# grissom.net
KiCad netlist of a schematic drawn in EAGLE
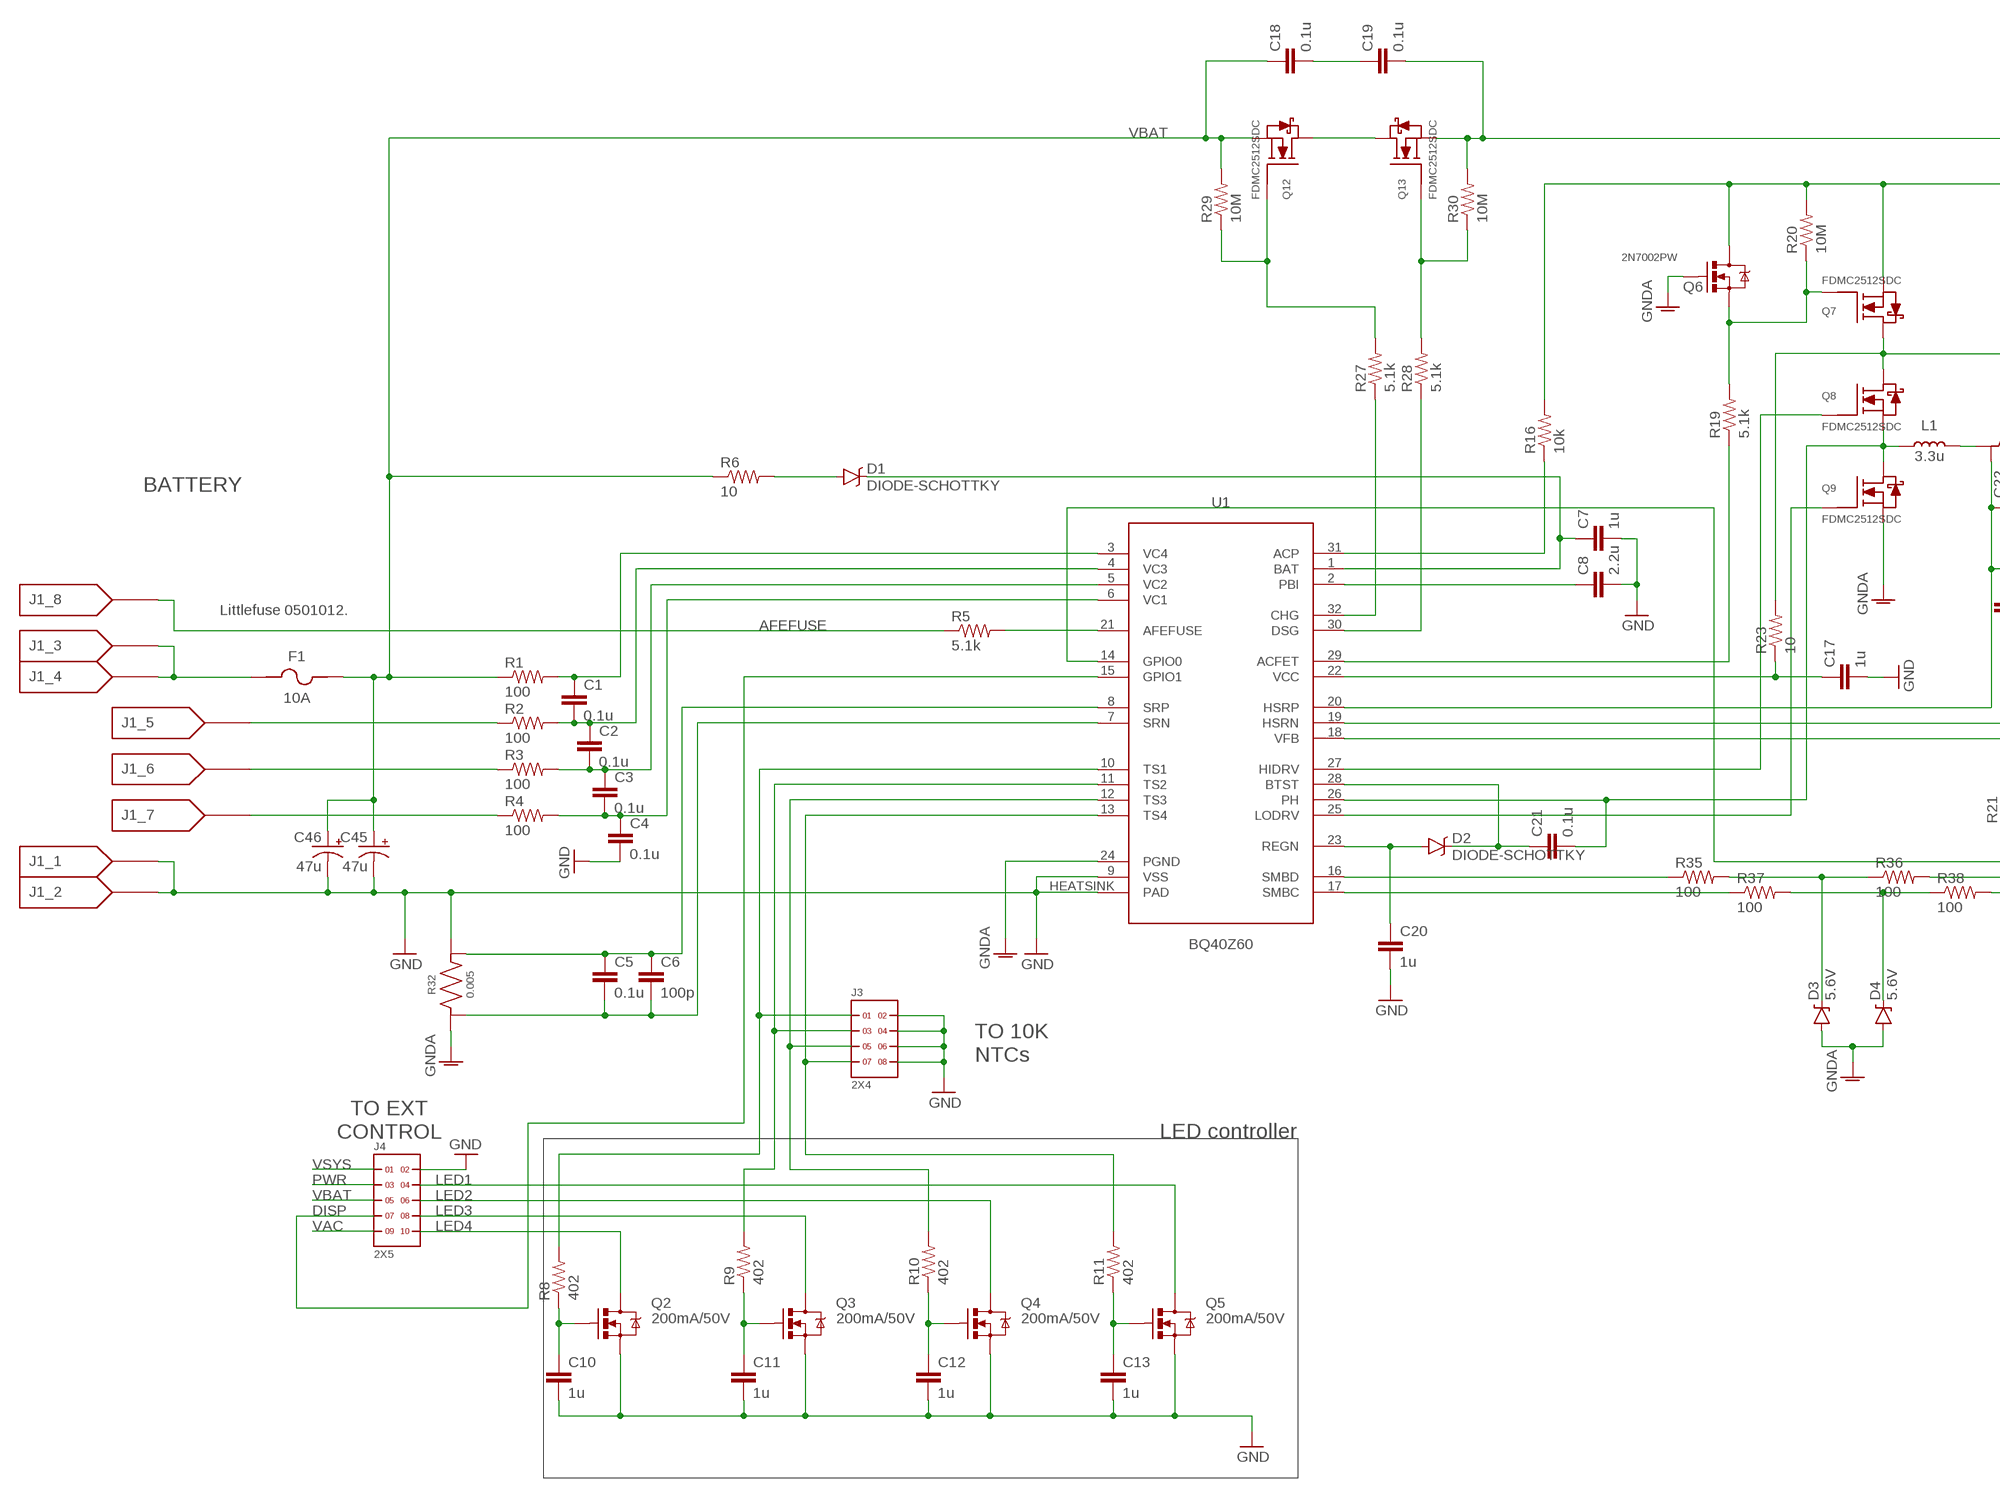
[diagram p0: schematic, sheet 1, part 1 of 2]
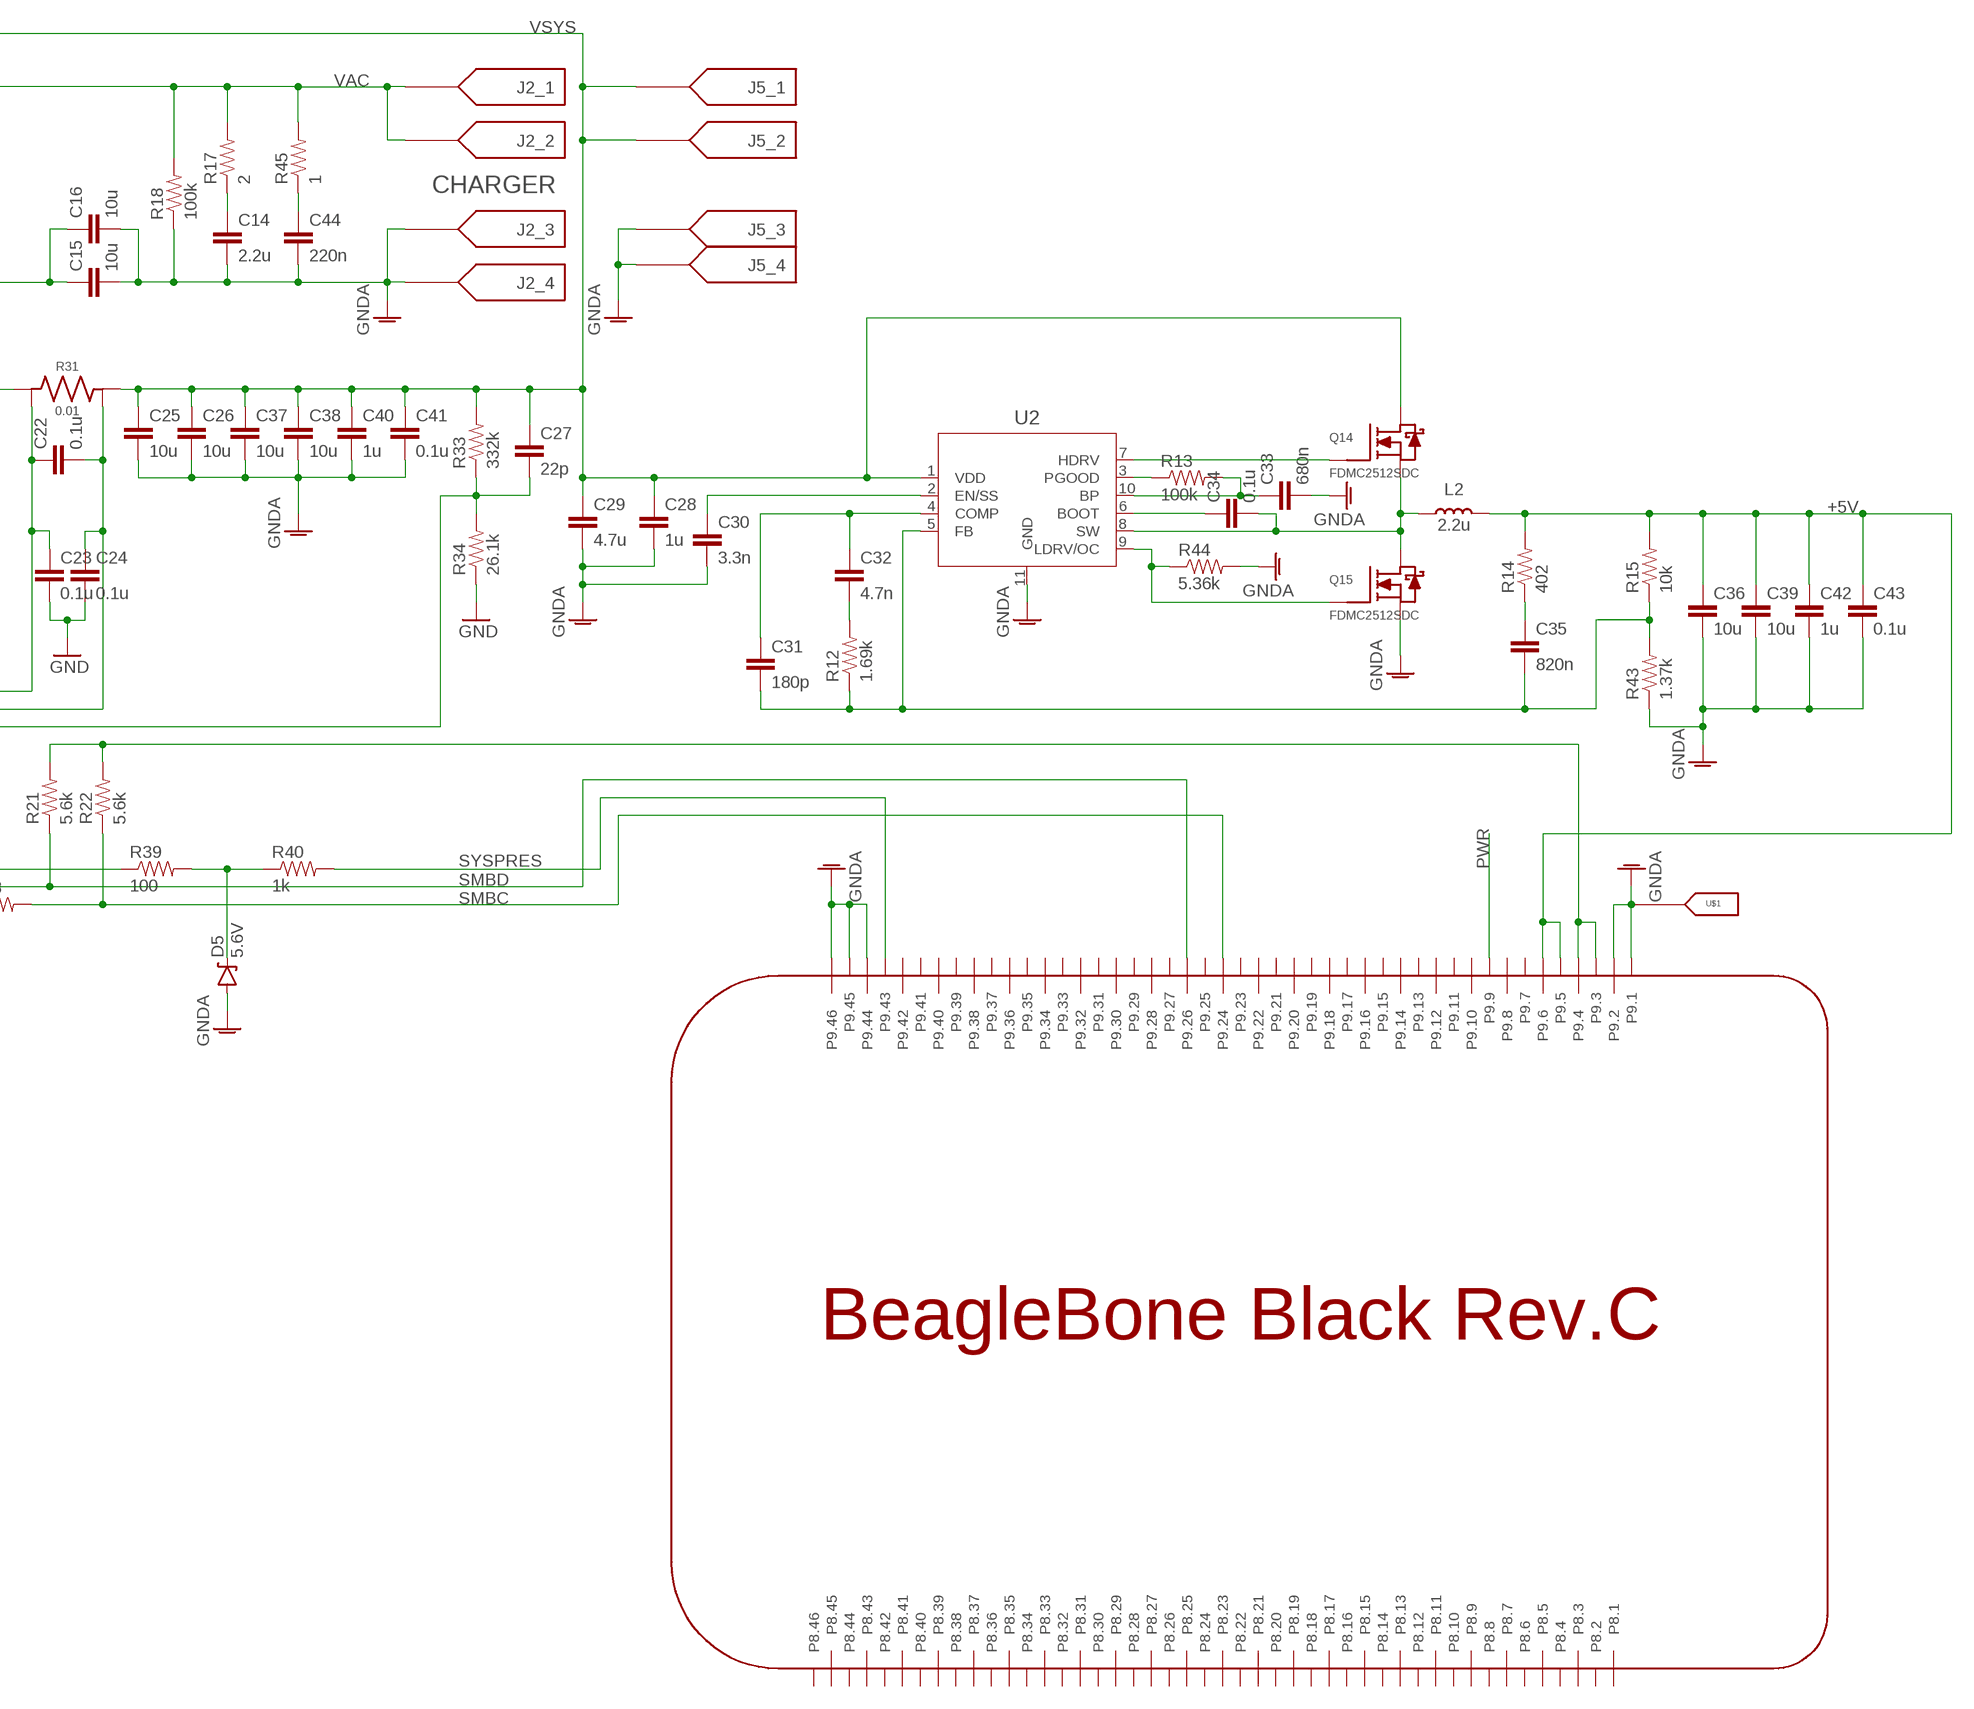
[diagram p1: schematic, sheet 1, part 2 of 2]

(export (version "E")
  (design (tool "Eeschema 10.0.6"))
  (components
    (comp (ref "C1")
      (value "0.1u")
      (footprint "eagle-import:0805")
      (libsource (lib "eagle-import") (part "CAP0805"))
    )
    (comp (ref "C2")
      (value "0.1u")
      (footprint "eagle-import:0805")
      (libsource (lib "eagle-import") (part "CAP0805"))
    )
    (comp (ref "C3")
      (value "0.1u")
      (footprint "eagle-import:0805")
      (libsource (lib "eagle-import") (part "CAP0805"))
    )
    (comp (ref "C4")
      (value "0.1u")
      (footprint "eagle-import:0805")
      (libsource (lib "eagle-import") (part "CAP0805"))
    )
    (comp (ref "C5")
      (value "0.1u")
      (footprint "eagle-import:0805")
      (libsource (lib "eagle-import") (part "CAP0805"))
    )
    (comp (ref "C6")
      (value "100p")
      (footprint "eagle-import:0805")
      (libsource (lib "eagle-import") (part "CAP0805"))
    )
    (comp (ref "C7")
      (value "1u")
      (footprint "eagle-import:0805")
      (libsource (lib "eagle-import") (part "CAP0805"))
    )
    (comp (ref "C8")
      (value "2.2u")
      (footprint "eagle-import:0805")
      (libsource (lib "eagle-import") (part "CAP0805"))
    )
    (comp (ref "C10")
      (value "1u")
      (footprint "eagle-import:0805")
      (libsource (lib "eagle-import") (part "CAP0805"))
    )
    (comp (ref "C11")
      (value "1u")
      (footprint "eagle-import:0805")
      (libsource (lib "eagle-import") (part "CAP0805"))
    )
    (comp (ref "C12")
      (value "1u")
      (footprint "eagle-import:0805")
      (libsource (lib "eagle-import") (part "CAP0805"))
    )
    (comp (ref "C13")
      (value "1u")
      (footprint "eagle-import:0805")
      (libsource (lib "eagle-import") (part "CAP0805"))
    )
    (comp (ref "C14")
      (value "2.2u")
      (footprint "eagle-import:0805")
      (libsource (lib "eagle-import") (part "CAP0805"))
    )
    (comp (ref "C15")
      (value "10u")
      (footprint "eagle-import:1206")
      (libsource (lib "eagle-import") (part "CAP1206"))
    )
    (comp (ref "C16")
      (value "10u")
      (footprint "eagle-import:1206")
      (libsource (lib "eagle-import") (part "CAP1206"))
    )
    (comp (ref "C17")
      (value "1u")
      (footprint "eagle-import:0805")
      (libsource (lib "eagle-import") (part "CAP0805"))
    )
    (comp (ref "C18")
      (value "0.1u")
      (footprint "eagle-import:0805")
      (libsource (lib "eagle-import") (part "CAP0805"))
    )
    (comp (ref "C19")
      (value "0.1u")
      (footprint "eagle-import:0805")
      (libsource (lib "eagle-import") (part "CAP0805"))
    )
    (comp (ref "C20")
      (value "1u")
      (footprint "eagle-import:0805")
      (libsource (lib "eagle-import") (part "CAP0805"))
    )
    (comp (ref "C21")
      (value "0.1u")
      (footprint "eagle-import:0805")
      (libsource (lib "eagle-import") (part "CAP0805"))
    )
    (comp (ref "C22")
      (value "0.1u")
      (footprint "eagle-import:0805")
      (libsource (lib "eagle-import") (part "CAP0805"))
    )
    (comp (ref "C23")
      (value "0.1u")
      (footprint "eagle-import:0805")
      (libsource (lib "eagle-import") (part "CAP0805"))
    )
    (comp (ref "C24")
      (value "0.1u")
      (footprint "eagle-import:0805")
      (libsource (lib "eagle-import") (part "CAP0805"))
    )
    (comp (ref "C25")
      (value "10u")
      (footprint "eagle-import:1206")
      (libsource (lib "eagle-import") (part "CAP1206"))
    )
    (comp (ref "C26")
      (value "10u")
      (footprint "eagle-import:1206")
      (libsource (lib "eagle-import") (part "CAP1206"))
    )
    (comp (ref "C27")
      (value "22p")
      (footprint "eagle-import:0805")
      (libsource (lib "eagle-import") (part "CAP0805"))
    )
    (comp (ref "C28")
      (value "1u")
      (footprint "eagle-import:0805")
      (libsource (lib "eagle-import") (part "CAP0805"))
    )
    (comp (ref "C29")
      (value "4.7u")
      (footprint "eagle-import:0805")
      (libsource (lib "eagle-import") (part "CAP0805"))
    )
    (comp (ref "C30")
      (value "3.3n")
      (footprint "eagle-import:0805")
      (libsource (lib "eagle-import") (part "CAP0805"))
    )
    (comp (ref "C31")
      (value "180p")
      (footprint "eagle-import:0805")
      (libsource (lib "eagle-import") (part "CAP0805"))
    )
    (comp (ref "C32")
      (value "4.7n")
      (footprint "eagle-import:0805")
      (libsource (lib "eagle-import") (part "CAP0805"))
    )
    (comp (ref "C33")
      (value "680n")
      (footprint "eagle-import:0805")
      (libsource (lib "eagle-import") (part "CAP0805"))
    )
    (comp (ref "C34")
      (value "0.1u")
      (footprint "eagle-import:0805")
      (libsource (lib "eagle-import") (part "CAP0805"))
    )
    (comp (ref "C35")
      (value "820n")
      (footprint "eagle-import:0805")
      (libsource (lib "eagle-import") (part "CAP0805"))
    )
    (comp (ref "C36")
      (value "10u")
      (footprint "eagle-import:1206")
      (libsource (lib "eagle-import") (part "CAP1206"))
    )
    (comp (ref "C37")
      (value "10u")
      (footprint "eagle-import:1206")
      (libsource (lib "eagle-import") (part "CAP1206"))
    )
    (comp (ref "C38")
      (value "10u")
      (footprint "eagle-import:1206")
      (libsource (lib "eagle-import") (part "CAP1206"))
    )
    (comp (ref "C39")
      (value "10u")
      (footprint "eagle-import:1206")
      (libsource (lib "eagle-import") (part "CAP1206"))
    )
    (comp (ref "C40")
      (value "1u")
      (footprint "eagle-import:1206")
      (libsource (lib "eagle-import") (part "CAP1206"))
    )
    (comp (ref "C41")
      (value "0.1u")
      (footprint "eagle-import:1206")
      (libsource (lib "eagle-import") (part "CAP1206"))
    )
    (comp (ref "C42")
      (value "1u")
      (footprint "eagle-import:1206")
      (libsource (lib "eagle-import") (part "CAP1206"))
    )
    (comp (ref "C43")
      (value "0.1u")
      (footprint "eagle-import:1206")
      (libsource (lib "eagle-import") (part "CAP1206"))
    )
    (comp (ref "C44")
      (value "220n")
      (footprint "eagle-import:0805")
      (libsource (lib "eagle-import") (part "CAP0805"))
    )
    (comp (ref "C45")
      (value "47u")
      (footprint "eagle-import:CPOL-RADIAL-10UF-25V")
      (libsource (lib "eagle-import") (part "CAP_POLPTH2"))
    )
    (comp (ref "C46")
      (value "47u")
      (footprint "eagle-import:CPOL-RADIAL-10UF-25V")
      (libsource (lib "eagle-import") (part "CAP_POLPTH2"))
    )
    (comp (ref "D1")
      (value "DIODE-SCHOTTKY")
      (footprint "eagle-import:SOT23-3")
      (libsource (lib "eagle-import") (part "DIODE-SCHOTTKY"))
    )
    (comp (ref "D2")
      (value "DIODE-SCHOTTKY")
      (footprint "eagle-import:SOT23-3")
      (libsource (lib "eagle-import") (part "DIODE-SCHOTTKY"))
    )
    (comp (ref "D3")
      (value "5.6V")
      (footprint "eagle-import:SOD-323")
      (libsource (lib "eagle-import") (part "DIODE-ZENER5.6V"))
    )
    (comp (ref "D4")
      (value "5.6V")
      (footprint "eagle-import:SOD-323")
      (libsource (lib "eagle-import") (part "DIODE-ZENER5.6V"))
    )
    (comp (ref "D5")
      (value "5.6V")
      (footprint "eagle-import:SOD-323")
      (libsource (lib "eagle-import") (part "DIODE-ZENER5.6V"))
    )
    (comp (ref "F1")
      (value "10A")
      (footprint "eagle-import:LITTELFUSE_501")
      (libsource (lib "eagle-import") (part "LITTELFUSE_501"))
    )
    (comp (ref "J1")
      (value "105314-X208")
      (footprint "eagle-import:105314-X208")
      (libsource (lib "eagle-import") (part "105314-X208"))
    )
    (comp (ref "J2")
      (value "105314-X204")
      (footprint "eagle-import:105314-X204")
      (libsource (lib "eagle-import") (part "105314-X204"))
    )
    (comp (ref "J3")
      (value "2X4")
      (footprint "eagle-import:2X4")
      (libsource (lib "eagle-import") (part "2X4"))
    )
    (comp (ref "J4")
      (value "2X5")
      (footprint "eagle-import:2X5")
      (libsource (lib "eagle-import") (part "2X5"))
    )
    (comp (ref "J5")
      (value "105314-X204")
      (footprint "eagle-import:105314-X204")
      (libsource (lib "eagle-import") (part "105314-X204"))
    )
    (comp (ref "L1")
      (value "3.3u")
      (footprint "eagle-import:BOURNS_SRP7028A")
      (libsource (lib "eagle-import") (part "BOURNS_SRP7028A"))
    )
    (comp (ref "L2")
      (value "2.2u")
      (footprint "eagle-import:BOURNS_SRP7028A")
      (libsource (lib "eagle-import") (part "BOURNS_SRP7028A"))
    )
    (comp (ref "PCB1")
      (value "BEAGLEBONE_BLACK_BLANK")
      (footprint "eagle-import:BEAGLEBONE_BLACK_BLANK")
      (libsource (lib "eagle-import") (part "BEAGLEBONE_BLACK_BLANK"))
    )
    (comp (ref "Q2")
      (value "200mA/50V")
      (footprint "eagle-import:SOT23-3")
      (libsource (lib "eagle-import") (part "MOSFET-NCHANNELBSS138"))
    )
    (comp (ref "Q3")
      (value "200mA/50V")
      (footprint "eagle-import:SOT23-3")
      (libsource (lib "eagle-import") (part "MOSFET-NCHANNELBSS138"))
    )
    (comp (ref "Q4")
      (value "200mA/50V")
      (footprint "eagle-import:SOT23-3")
      (libsource (lib "eagle-import") (part "MOSFET-NCHANNELBSS138"))
    )
    (comp (ref "Q5")
      (value "200mA/50V")
      (footprint "eagle-import:SOT23-3")
      (libsource (lib "eagle-import") (part "MOSFET-NCHANNELBSS138"))
    )
    (comp (ref "Q6")
      (value "2N7002PW")
      (footprint "eagle-import:SOT323")
      (libsource (lib "eagle-import") (part "MOSFET-NCHANNEL2N7002PW"))
    )
    (comp (ref "Q7")
      (value "FDMC2512SDC")
      (footprint "eagle-import:MO240")
      (libsource (lib "eagle-import") (part "FDMC2512SDC"))
    )
    (comp (ref "Q8")
      (value "FDMC2512SDC")
      (footprint "eagle-import:MO240")
      (libsource (lib "eagle-import") (part "FDMC2512SDC"))
    )
    (comp (ref "Q9")
      (value "FDMC2512SDC")
      (footprint "eagle-import:MO240")
      (libsource (lib "eagle-import") (part "FDMC2512SDC"))
    )
    (comp (ref "Q12")
      (value "FDMC2512SDC")
      (footprint "eagle-import:MO240")
      (libsource (lib "eagle-import") (part "FDMC2512SDC"))
    )
    (comp (ref "Q13")
      (value "FDMC2512SDC")
      (footprint "eagle-import:MO240")
      (libsource (lib "eagle-import") (part "FDMC2512SDC"))
    )
    (comp (ref "Q14")
      (value "FDMC2512SDC")
      (footprint "eagle-import:MO240")
      (libsource (lib "eagle-import") (part "FDMC2512SDC"))
    )
    (comp (ref "Q15")
      (value "FDMC2512SDC")
      (footprint "eagle-import:MO240")
      (libsource (lib "eagle-import") (part "FDMC2512SDC"))
    )
    (comp (ref "R1")
      (value "100")
      (footprint "eagle-import:0805")
      (libsource (lib "eagle-import") (part "RESISTOR0805-RES"))
    )
    (comp (ref "R2")
      (value "100")
      (footprint "eagle-import:0805")
      (libsource (lib "eagle-import") (part "RESISTOR0805-RES"))
    )
    (comp (ref "R3")
      (value "100")
      (footprint "eagle-import:0805")
      (libsource (lib "eagle-import") (part "RESISTOR0805-RES"))
    )
    (comp (ref "R4")
      (value "100")
      (footprint "eagle-import:0805")
      (libsource (lib "eagle-import") (part "RESISTOR0805-RES"))
    )
    (comp (ref "R5")
      (value "5.1k")
      (footprint "eagle-import:0805")
      (libsource (lib "eagle-import") (part "RESISTOR0805-RES"))
    )
    (comp (ref "R6")
      (value "10")
      (footprint "eagle-import:1206")
      (libsource (lib "eagle-import") (part "RESISTOR1206"))
    )
    (comp (ref "R8")
      (value "402")
      (footprint "eagle-import:0805")
      (libsource (lib "eagle-import") (part "RESISTOR0805-RES"))
    )
    (comp (ref "R9")
      (value "402")
      (footprint "eagle-import:0805")
      (libsource (lib "eagle-import") (part "RESISTOR0805-RES"))
    )
    (comp (ref "R10")
      (value "402")
      (footprint "eagle-import:0805")
      (libsource (lib "eagle-import") (part "RESISTOR0805-RES"))
    )
    (comp (ref "R11")
      (value "402")
      (footprint "eagle-import:0805")
      (libsource (lib "eagle-import") (part "RESISTOR0805-RES"))
    )
    (comp (ref "R12")
      (value "1.69k")
      (footprint "eagle-import:0805")
      (libsource (lib "eagle-import") (part "RESISTOR0805-RES"))
    )
    (comp (ref "R13")
      (value "100k")
      (footprint "eagle-import:0805")
      (libsource (lib "eagle-import") (part "RESISTOR0805-RES"))
    )
    (comp (ref "R14")
      (value "402")
      (footprint "eagle-import:0805")
      (libsource (lib "eagle-import") (part "RESISTOR0805-RES"))
    )
    (comp (ref "R15")
      (value "10k")
      (footprint "eagle-import:0805")
      (libsource (lib "eagle-import") (part "RESISTOR0805-RES"))
    )
    (comp (ref "R16")
      (value "10k")
      (footprint "eagle-import:0805")
      (libsource (lib "eagle-import") (part "RESISTOR0805-RES"))
    )
    (comp (ref "R17")
      (value "2")
      (footprint "eagle-import:0805")
      (libsource (lib "eagle-import") (part "RESISTOR0805-RES"))
    )
    (comp (ref "R18")
      (value "100k")
      (footprint "eagle-import:0805")
      (libsource (lib "eagle-import") (part "RESISTOR0805-RES"))
    )
    (comp (ref "R19")
      (value "5.1k")
      (footprint "eagle-import:0805")
      (libsource (lib "eagle-import") (part "RESISTOR0805-RES"))
    )
    (comp (ref "R20")
      (value "10M")
      (footprint "eagle-import:0805")
      (libsource (lib "eagle-import") (part "RESISTOR0805-RES"))
    )
    (comp (ref "R21")
      (value "5.6k")
      (footprint "eagle-import:0805")
      (libsource (lib "eagle-import") (part "RESISTOR0805-RES"))
    )
    (comp (ref "R22")
      (value "5.6k")
      (footprint "eagle-import:0805")
      (libsource (lib "eagle-import") (part "RESISTOR0805-RES"))
    )
    (comp (ref "R23")
      (value "10")
      (footprint "eagle-import:0805")
      (libsource (lib "eagle-import") (part "RESISTOR0805-RES"))
    )
    (comp (ref "R27")
      (value "5.1k")
      (footprint "eagle-import:0805")
      (libsource (lib "eagle-import") (part "RESISTOR0805-RES"))
    )
    (comp (ref "R28")
      (value "5.1k")
      (footprint "eagle-import:0805")
      (libsource (lib "eagle-import") (part "RESISTOR0805-RES"))
    )
    (comp (ref "R29")
      (value "10M")
      (footprint "eagle-import:0805")
      (libsource (lib "eagle-import") (part "RESISTOR0805-RES"))
    )
    (comp (ref "R30")
      (value "10M")
      (footprint "eagle-import:0805")
      (libsource (lib "eagle-import") (part "RESISTOR0805-RES"))
    )
    (comp (ref "R31")
      (value "0.01")
      (footprint "eagle-import:1206_4T")
      (libsource (lib "eagle-import") (part "OHMITE_FC4L32"))
    )
    (comp (ref "R32")
      (value "0.005")
      (footprint "eagle-import:0612_4T")
      (libsource (lib "eagle-import") (part "VISHAY_WSK0612"))
    )
    (comp (ref "R33")
      (value "332k")
      (footprint "eagle-import:0805")
      (libsource (lib "eagle-import") (part "RESISTOR0805-RES"))
    )
    (comp (ref "R34")
      (value "26.1k")
      (footprint "eagle-import:0805")
      (libsource (lib "eagle-import") (part "RESISTOR0805-RES"))
    )
    (comp (ref "R35")
      (value "100")
      (footprint "eagle-import:0805")
      (libsource (lib "eagle-import") (part "RESISTOR0805-RES"))
    )
    (comp (ref "R36")
      (value "100")
      (footprint "eagle-import:0805")
      (libsource (lib "eagle-import") (part "RESISTOR0805-RES"))
    )
    (comp (ref "R37")
      (value "100")
      (footprint "eagle-import:0805")
      (libsource (lib "eagle-import") (part "RESISTOR0805-RES"))
    )
    (comp (ref "R38")
      (value "100")
      (footprint "eagle-import:0805")
      (libsource (lib "eagle-import") (part "RESISTOR0805-RES"))
    )
    (comp (ref "R39")
      (value "100")
      (footprint "eagle-import:0805")
      (libsource (lib "eagle-import") (part "RESISTOR0805-RES"))
    )
    (comp (ref "R40")
      (value "1k")
      (footprint "eagle-import:0805")
      (libsource (lib "eagle-import") (part "RESISTOR0805-RES"))
    )
    (comp (ref "R43")
      (value "1.37k")
      (footprint "eagle-import:0805")
      (libsource (lib "eagle-import") (part "RESISTOR0805-RES"))
    )
    (comp (ref "R44")
      (value "5.36k")
      (footprint "eagle-import:0805")
      (libsource (lib "eagle-import") (part "RESISTOR0805-RES"))
    )
    (comp (ref "R45")
      (value "1")
      (footprint "eagle-import:0805")
      (libsource (lib "eagle-import") (part "RESISTOR0805-RES"))
    )
    (comp (ref "U$1")
      (value "SU_LOGO-DUMMY2")
      (footprint "eagle-import:SU_LOGO_SS")
      (libsource (lib "eagle-import") (part "SU_LOGO-DUMMY2"))
    )
    (comp (ref "U1")
      (value "BQ40Z60")
      (footprint "eagle-import:QFN32")
      (libsource (lib "eagle-import") (part "BQ40Z60"))
    )
    (comp (ref "U2")
      (value "TPS40305DRCR")
      (footprint "eagle-import:S-PVSON-N10")
      (libsource (lib "eagle-import") (part "TPS40305DRCR"))
    )
  )
  (nets
    (net (code "1") (name "/+5V") (class "Default")
      (node (ref "C36") (pin "1") (pinfunction "1_1") (pintype "passive"))
      (node (ref "C39") (pin "1") (pinfunction "1_1") (pintype "passive"))
      (node (ref "C42") (pin "1") (pinfunction "1_1") (pintype "passive"))
      (node (ref "C43") (pin "1") (pinfunction "1_1") (pintype "passive"))
      (node (ref "L2") (pin "P$2") (pinfunction "P$2_P$2") (pintype "bidirectional"))
      (node (ref "PCB1") (pin "P9.5") (pinfunction "P9.5_P9.5") (pintype "bidirectional"))
      (node (ref "PCB1") (pin "P9.6") (pinfunction "P9.6_P9.6") (pintype "bidirectional"))
      (node (ref "R14") (pin "2") (pinfunction "2_2") (pintype "passive"))
      (node (ref "R15") (pin "2") (pinfunction "2_2") (pintype "passive"))
    )
    (net (code "2") (name "/AFEFUSE") (class "Default")
      (node (ref "J1") (pin "P$8") (pinfunction "P$1_P$8") (pintype "bidirectional"))
      (node (ref "R5") (pin "1") (pinfunction "1_1") (pintype "passive"))
    )
    (net (code "3") (name "/DISP") (class "Default")
      (node (ref "J4") (pin "7") (pinfunction "7_7") (pintype "bidirectional"))
      (node (ref "U1") (pin "15") (pinfunction "GPIO1_15") (pintype "bidirectional"))
    )
    (net (code "4") (name "/LED1") (class "Default")
      (node (ref "J4") (pin "4") (pinfunction "4_4") (pintype "bidirectional"))
      (node (ref "Q5") (pin "3") (pinfunction "D_3") (pintype "passive"))
    )
    (net (code "5") (name "/LED2") (class "Default")
      (node (ref "J4") (pin "6") (pinfunction "6_6") (pintype "bidirectional"))
      (node (ref "Q4") (pin "3") (pinfunction "D_3") (pintype "passive"))
    )
    (net (code "6") (name "/LED3") (class "Default")
      (node (ref "J4") (pin "8") (pinfunction "8_8") (pintype "bidirectional"))
      (node (ref "Q3") (pin "3") (pinfunction "D_3") (pintype "passive"))
    )
    (net (code "7") (name "/LED4") (class "Default")
      (node (ref "J4") (pin "10") (pinfunction "10_10") (pintype "bidirectional"))
      (node (ref "Q2") (pin "3") (pinfunction "D_3") (pintype "passive"))
    )
    (net (code "8") (name "/PWR") (class "Default")
      (node (ref "J4") (pin "3") (pinfunction "3_3") (pintype "bidirectional"))
      (node (ref "PCB1") (pin "P9.9") (pinfunction "P9.9_P9.9") (pintype "bidirectional"))
    )
    (net (code "9") (name "/VAC") (class "Default")
      (node (ref "J2") (pin "P$1") (pinfunction "P$1_P$1") (pintype "bidirectional"))
      (node (ref "J2") (pin "P$2") (pinfunction "P$1_P$2") (pintype "bidirectional"))
      (node (ref "J4") (pin "9") (pinfunction "9_9") (pintype "bidirectional"))
      (node (ref "Q6") (pin "3") (pinfunction "D_3") (pintype "passive"))
      (node (ref "Q7") (pin "P$1") (pinfunction "S_P$1") (pintype "bidirectional"))
      (node (ref "Q7") (pin "P$2") (pinfunction "S_P$2") (pintype "bidirectional"))
      (node (ref "Q7") (pin "P$3") (pinfunction "S_P$3") (pintype "bidirectional"))
      (node (ref "R16") (pin "2") (pinfunction "2_2") (pintype "passive"))
      (node (ref "R17") (pin "2") (pinfunction "2_2") (pintype "passive"))
      (node (ref "R18") (pin "2") (pinfunction "2_2") (pintype "passive"))
      (node (ref "R20") (pin "2") (pinfunction "2_2") (pintype "passive"))
      (node (ref "R45") (pin "2") (pinfunction "2_2") (pintype "passive"))
    )
    (net (code "10") (name "/VBAT") (class "Default")
      (node (ref "C18") (pin "1") (pinfunction "1_1") (pintype "passive"))
      (node (ref "C45") (pin "1") (pinfunction "+_1") (pintype "passive"))
      (node (ref "C46") (pin "1") (pinfunction "+_1") (pintype "passive"))
      (node (ref "F1") (pin "P$2") (pinfunction "P$2_P$2") (pintype "bidirectional"))
      (node (ref "J4") (pin "5") (pinfunction "5_5") (pintype "bidirectional"))
      (node (ref "Q12") (pin "P$1") (pinfunction "S_P$1") (pintype "bidirectional"))
      (node (ref "Q12") (pin "P$2") (pinfunction "S_P$2") (pintype "bidirectional"))
      (node (ref "Q12") (pin "P$3") (pinfunction "S_P$3") (pintype "bidirectional"))
      (node (ref "R1") (pin "1") (pinfunction "1_1") (pintype "passive"))
      (node (ref "R29") (pin "2") (pinfunction "2_2") (pintype "passive"))
      (node (ref "R6") (pin "1") (pinfunction "1_1") (pintype "passive"))
    )
    (net (code "11") (name "/VSYS") (class "Default")
      (node (ref "C19") (pin "2") (pinfunction "2_2") (pintype "passive"))
      (node (ref "C25") (pin "1") (pinfunction "1_1") (pintype "passive"))
      (node (ref "C26") (pin "1") (pinfunction "1_1") (pintype "passive"))
      (node (ref "C27") (pin "1") (pinfunction "1_1") (pintype "passive"))
      (node (ref "C28") (pin "1") (pinfunction "1_1") (pintype "passive"))
      (node (ref "C29") (pin "1") (pinfunction "1_1") (pintype "passive"))
      (node (ref "C37") (pin "1") (pinfunction "1_1") (pintype "passive"))
      (node (ref "C38") (pin "1") (pinfunction "1_1") (pintype "passive"))
      (node (ref "C40") (pin "1") (pinfunction "1_1") (pintype "passive"))
      (node (ref "C41") (pin "1") (pinfunction "1_1") (pintype "passive"))
      (node (ref "J4") (pin "1") (pinfunction "1_1") (pintype "bidirectional"))
      (node (ref "J5") (pin "P$1") (pinfunction "P$1_P$1") (pintype "bidirectional"))
      (node (ref "J5") (pin "P$2") (pinfunction "P$1_P$2") (pintype "bidirectional"))
      (node (ref "Q13") (pin "P$1") (pinfunction "S_P$1") (pintype "bidirectional"))
      (node (ref "Q13") (pin "P$2") (pinfunction "S_P$2") (pintype "bidirectional"))
      (node (ref "Q13") (pin "P$3") (pinfunction "S_P$3") (pintype "bidirectional"))
      (node (ref "Q14") (pin "P$5") (pinfunction "D_P$5") (pintype "bidirectional"))
      (node (ref "Q14") (pin "P$6") (pinfunction "D_P$6") (pintype "bidirectional"))
      (node (ref "Q14") (pin "P$7") (pinfunction "D_P$7") (pintype "bidirectional"))
      (node (ref "Q14") (pin "P$8") (pinfunction "D_P$8") (pintype "bidirectional"))
      (node (ref "Q14") (pin "PAD") (pinfunction "D_PAD") (pintype "bidirectional"))
      (node (ref "R30") (pin "2") (pinfunction "2_2") (pintype "passive"))
      (node (ref "R31") (pin "P$2") (pinfunction "P$2_P$2") (pintype "bidirectional"))
      (node (ref "R33") (pin "2") (pinfunction "2_2") (pintype "passive"))
      (node (ref "U2") (pin "1") (pinfunction "VDD_1") (pintype "passive"))
    )
    (net (code "12") (name "GND") (class "Default")
      (node (ref "C10") (pin "2") (pinfunction "2_2") (pintype "passive"))
      (node (ref "C11") (pin "2") (pinfunction "2_2") (pintype "passive"))
      (node (ref "C12") (pin "2") (pinfunction "2_2") (pintype "passive"))
      (node (ref "C13") (pin "2") (pinfunction "2_2") (pintype "passive"))
      (node (ref "C17") (pin "2") (pinfunction "2_2") (pintype "passive"))
      (node (ref "C20") (pin "2") (pinfunction "2_2") (pintype "passive"))
      (node (ref "C23") (pin "2") (pinfunction "2_2") (pintype "passive"))
      (node (ref "C24") (pin "2") (pinfunction "2_2") (pintype "passive"))
      (node (ref "C4") (pin "2") (pinfunction "2_2") (pintype "passive"))
      (node (ref "C45") (pin "2") (pinfunction "-_2") (pintype "passive"))
      (node (ref "C46") (pin "2") (pinfunction "-_2") (pintype "passive"))
      (node (ref "C7") (pin "2") (pinfunction "2_2") (pintype "passive"))
      (node (ref "C8") (pin "2") (pinfunction "2_2") (pintype "passive"))
      (node (ref "J1") (pin "P$1") (pinfunction "P$1_P$1") (pintype "bidirectional"))
      (node (ref "J1") (pin "P$2") (pinfunction "P$1_P$2") (pintype "bidirectional"))
      (node (ref "J3") (pin "2") (pinfunction "2_2") (pintype "bidirectional"))
      (node (ref "J3") (pin "4") (pinfunction "4_4") (pintype "bidirectional"))
      (node (ref "J3") (pin "6") (pinfunction "6_6") (pintype "bidirectional"))
      (node (ref "J3") (pin "8") (pinfunction "8_8") (pintype "bidirectional"))
      (node (ref "J4") (pin "2") (pinfunction "2_2") (pintype "bidirectional"))
      (node (ref "Q2") (pin "2") (pinfunction "S_2") (pintype "passive"))
      (node (ref "Q3") (pin "2") (pinfunction "S_2") (pintype "passive"))
      (node (ref "Q4") (pin "2") (pinfunction "S_2") (pintype "passive"))
      (node (ref "Q5") (pin "2") (pinfunction "S_2") (pintype "passive"))
      (node (ref "R32") (pin "P$2") (pinfunction "P$2_P$2") (pintype "bidirectional"))
      (node (ref "R34") (pin "1") (pinfunction "1_1") (pintype "passive"))
      (node (ref "U1") (pin "9") (pinfunction "VSS_9") (pintype "bidirectional"))
      (node (ref "U1") (pin "HEATSINK") (pinfunction "PAD_HEATSINK") (pintype "bidirectional"))
    )
    (net (code "13") (name "GNDA") (class "Default")
      (node (ref "C14") (pin "2") (pinfunction "2_2") (pintype "passive"))
      (node (ref "C15") (pin "2") (pinfunction "2_2") (pintype "passive"))
      (node (ref "C16") (pin "2") (pinfunction "2_2") (pintype "passive"))
      (node (ref "C25") (pin "2") (pinfunction "2_2") (pintype "passive"))
      (node (ref "C26") (pin "2") (pinfunction "2_2") (pintype "passive"))
      (node (ref "C28") (pin "2") (pinfunction "2_2") (pintype "passive"))
      (node (ref "C29") (pin "2") (pinfunction "2_2") (pintype "passive"))
      (node (ref "C30") (pin "2") (pinfunction "2_2") (pintype "passive"))
      (node (ref "C33") (pin "2") (pinfunction "2_2") (pintype "passive"))
      (node (ref "C36") (pin "2") (pinfunction "2_2") (pintype "passive"))
      (node (ref "C37") (pin "2") (pinfunction "2_2") (pintype "passive"))
      (node (ref "C38") (pin "2") (pinfunction "2_2") (pintype "passive"))
      (node (ref "C39") (pin "2") (pinfunction "2_2") (pintype "passive"))
      (node (ref "C40") (pin "2") (pinfunction "2_2") (pintype "passive"))
      (node (ref "C41") (pin "2") (pinfunction "2_2") (pintype "passive"))
      (node (ref "C42") (pin "2") (pinfunction "2_2") (pintype "passive"))
      (node (ref "C43") (pin "2") (pinfunction "2_2") (pintype "passive"))
      (node (ref "C44") (pin "2") (pinfunction "2_2") (pintype "passive"))
      (node (ref "D3") (pin "A") (pinfunction "A_A") (pintype "passive"))
      (node (ref "D4") (pin "A") (pinfunction "A_A") (pintype "passive"))
      (node (ref "D5") (pin "A") (pinfunction "A_A") (pintype "passive"))
      (node (ref "J2") (pin "P$3") (pinfunction "P$1_P$3") (pintype "bidirectional"))
      (node (ref "J2") (pin "P$4") (pinfunction "P$1_P$4") (pintype "bidirectional"))
      (node (ref "J5") (pin "P$3") (pinfunction "P$1_P$3") (pintype "bidirectional"))
      (node (ref "J5") (pin "P$4") (pinfunction "P$1_P$4") (pintype "bidirectional"))
      (node (ref "PCB1") (pin "P9.1") (pinfunction "P9.1_P9.1") (pintype "bidirectional"))
      (node (ref "PCB1") (pin "P9.2") (pinfunction "P9.2_P9.2") (pintype "bidirectional"))
      (node (ref "PCB1") (pin "P9.44") (pinfunction "P9.44_P9.44") (pintype "bidirectional"))
      (node (ref "PCB1") (pin "P9.45") (pinfunction "P9.45_P9.45") (pintype "bidirectional"))
      (node (ref "PCB1") (pin "P9.46") (pinfunction "P9.46_P9.46") (pintype "bidirectional"))
      (node (ref "Q15") (pin "P$1") (pinfunction "S_P$1") (pintype "bidirectional"))
      (node (ref "Q15") (pin "P$2") (pinfunction "S_P$2") (pintype "bidirectional"))
      (node (ref "Q15") (pin "P$3") (pinfunction "S_P$3") (pintype "bidirectional"))
      (node (ref "Q6") (pin "1") (pinfunction "G_1") (pintype "passive"))
      (node (ref "Q9") (pin "P$1") (pinfunction "S_P$1") (pintype "bidirectional"))
      (node (ref "Q9") (pin "P$2") (pinfunction "S_P$2") (pintype "bidirectional"))
      (node (ref "Q9") (pin "P$3") (pinfunction "S_P$3") (pintype "bidirectional"))
      (node (ref "R18") (pin "1") (pinfunction "1_1") (pintype "passive"))
      (node (ref "R32") (pin "P$1") (pinfunction "P$1_P$1") (pintype "bidirectional"))
      (node (ref "R43") (pin "1") (pinfunction "1_1") (pintype "passive"))
      (node (ref "R44") (pin "2") (pinfunction "2_2") (pintype "passive"))
      (node (ref "U$1") (pin "P$1") (pinfunction "P$1_P$1") (pintype "bidirectional"))
      (node (ref "U1") (pin "24") (pinfunction "PGND_24") (pintype "bidirectional"))
      (node (ref "U2") (pin "11") (pinfunction "GND_11") (pintype "passive"))
    )
    (net (code "14") (name "Net-(C14-Pad1)") (class "Default")
      (node (ref "C14") (pin "1") (pinfunction "1_1") (pintype "passive"))
      (node (ref "R17") (pin "1") (pinfunction "1_1") (pintype "passive"))
    )
    (net (code "15") (name "Net-(C15-Pad1)") (class "Default")
      (node (ref "C15") (pin "1") (pinfunction "1_1") (pintype "passive"))
      (node (ref "C16") (pin "1") (pinfunction "1_1") (pintype "passive"))
      (node (ref "Q7") (pin "P$5") (pinfunction "D_P$5") (pintype "bidirectional"))
      (node (ref "Q7") (pin "P$6") (pinfunction "D_P$6") (pintype "bidirectional"))
      (node (ref "Q7") (pin "P$7") (pinfunction "D_P$7") (pintype "bidirectional"))
      (node (ref "Q7") (pin "P$8") (pinfunction "D_P$8") (pintype "bidirectional"))
      (node (ref "Q7") (pin "PAD") (pinfunction "D_PAD") (pintype "bidirectional"))
      (node (ref "Q8") (pin "P$5") (pinfunction "D_P$5") (pintype "bidirectional"))
      (node (ref "Q8") (pin "P$6") (pinfunction "D_P$6") (pintype "bidirectional"))
      (node (ref "Q8") (pin "P$7") (pinfunction "D_P$7") (pintype "bidirectional"))
      (node (ref "Q8") (pin "P$8") (pinfunction "D_P$8") (pintype "bidirectional"))
      (node (ref "Q8") (pin "PAD") (pinfunction "D_PAD") (pintype "bidirectional"))
      (node (ref "R23") (pin "2") (pinfunction "2_2") (pintype "passive"))
    )
    (net (code "16") (name "Net-(C18-Pad2)") (class "Default")
      (node (ref "C18") (pin "2") (pinfunction "2_2") (pintype "passive"))
      (node (ref "C19") (pin "1") (pinfunction "1_1") (pintype "passive"))
    )
    (net (code "17") (name "Net-(C32-Pad2)") (class "Default")
      (node (ref "C32") (pin "2") (pinfunction "2_2") (pintype "passive"))
      (node (ref "R12") (pin "2") (pinfunction "2_2") (pintype "passive"))
    )
    (net (code "18") (name "Net-(C35-Pad1)") (class "Default")
      (node (ref "C35") (pin "1") (pinfunction "1_1") (pintype "passive"))
      (node (ref "R14") (pin "1") (pinfunction "1_1") (pintype "passive"))
    )
    (net (code "19") (name "Net-(C44-Pad1)") (class "Default")
      (node (ref "C44") (pin "1") (pinfunction "1_1") (pintype "passive"))
      (node (ref "R45") (pin "1") (pinfunction "1_1") (pintype "passive"))
    )
    (net (code "20") (name "Net-(D1-A-Pad1)") (class "Default")
      (node (ref "D1") (pin "1") (pinfunction "A_1") (pintype "passive"))
      (node (ref "D1") (pin "2") (pinfunction "A_2") (pintype "passive"))
      (node (ref "R6") (pin "2") (pinfunction "2_2") (pintype "passive"))
    )
    (net (code "21") (name "Net-(D1-C)") (class "Default")
      (node (ref "C7") (pin "1") (pinfunction "1_1") (pintype "passive"))
      (node (ref "D1") (pin "3") (pinfunction "C_3") (pintype "passive"))
      (node (ref "U1") (pin "1") (pinfunction "BAT_1") (pintype "bidirectional"))
    )
    (net (code "22") (name "Net-(D2-C)") (class "Default")
      (node (ref "C21") (pin "1") (pinfunction "1_1") (pintype "passive"))
      (node (ref "D2") (pin "3") (pinfunction "C_3") (pintype "passive"))
      (node (ref "U1") (pin "28") (pinfunction "BTST_28") (pintype "bidirectional"))
    )
    (net (code "23") (name "Net-(D3-PadC)") (class "Default")
      (node (ref "D3") (pin "C") (pinfunction "C_C") (pintype "passive"))
      (node (ref "R35") (pin "2") (pinfunction "2_2") (pintype "passive"))
      (node (ref "R36") (pin "1") (pinfunction "1_1") (pintype "passive"))
    )
    (net (code "24") (name "Net-(D4-PadC)") (class "Default")
      (node (ref "D4") (pin "C") (pinfunction "C_C") (pintype "passive"))
      (node (ref "R37") (pin "2") (pinfunction "2_2") (pintype "passive"))
      (node (ref "R38") (pin "1") (pinfunction "1_1") (pintype "passive"))
    )
    (net (code "25") (name "Net-(D5-PadC)") (class "Default")
      (node (ref "D5") (pin "C") (pinfunction "C_C") (pintype "passive"))
      (node (ref "R39") (pin "2") (pinfunction "2_2") (pintype "passive"))
      (node (ref "R40") (pin "1") (pinfunction "1_1") (pintype "passive"))
    )
    (net (code "26") (name "Net-(J1C-P$1)") (class "Default")
      (node (ref "F1") (pin "P$1") (pinfunction "P$1_P$1") (pintype "bidirectional"))
      (node (ref "J1") (pin "P$3") (pinfunction "P$1_P$3") (pintype "bidirectional"))
      (node (ref "J1") (pin "P$4") (pinfunction "P$1_P$4") (pintype "bidirectional"))
    )
    (net (code "27") (name "Net-(J1E-P$1)") (class "Default")
      (node (ref "J1") (pin "P$5") (pinfunction "P$1_P$5") (pintype "bidirectional"))
      (node (ref "R2") (pin "1") (pinfunction "1_1") (pintype "passive"))
    )
    (net (code "28") (name "Net-(J1F-P$1)") (class "Default")
      (node (ref "J1") (pin "P$6") (pinfunction "P$1_P$6") (pintype "bidirectional"))
      (node (ref "R3") (pin "1") (pinfunction "1_1") (pintype "passive"))
    )
    (net (code "29") (name "Net-(J1G-P$1)") (class "Default")
      (node (ref "J1") (pin "P$7") (pinfunction "P$1_P$7") (pintype "bidirectional"))
      (node (ref "R4") (pin "1") (pinfunction "1_1") (pintype "passive"))
    )
    (net (code "30") (name "Net-(L1-PadP$2)") (class "Default")
      (node (ref "L1") (pin "P$2") (pinfunction "P$2_P$2") (pintype "bidirectional"))
      (node (ref "R31") (pin "P$1") (pinfunction "P$1_P$1") (pintype "bidirectional"))
    )
    (net (code "31") (name "Net-(PCB1-PadP9.3)") (class "Default")
      (node (ref "PCB1") (pin "P9.3") (pinfunction "P9.3_P9.3") (pintype "bidirectional"))
      (node (ref "PCB1") (pin "P9.4") (pinfunction "P9.4_P9.4") (pintype "bidirectional"))
      (node (ref "R21") (pin "2") (pinfunction "2_2") (pintype "passive"))
      (node (ref "R22") (pin "2") (pinfunction "2_2") (pintype "passive"))
    )
    (net (code "32") (name "Net-(PCB1-PadP9.24)") (class "Default")
      (node (ref "PCB1") (pin "P9.24") (pinfunction "P9.24_P9.24") (pintype "bidirectional"))
      (node (ref "R22") (pin "1") (pinfunction "1_1") (pintype "passive"))
      (node (ref "R38") (pin "2") (pinfunction "2_2") (pintype "passive"))
    )
    (net (code "33") (name "Net-(PCB1-PadP9.26)") (class "Default")
      (node (ref "PCB1") (pin "P9.26") (pinfunction "P9.26_P9.26") (pintype "bidirectional"))
      (node (ref "R21") (pin "1") (pinfunction "1_1") (pintype "passive"))
      (node (ref "R36") (pin "2") (pinfunction "2_2") (pintype "passive"))
    )
    (net (code "34") (name "Net-(PCB1-PadP9.43)") (class "Default")
      (node (ref "PCB1") (pin "P9.43") (pinfunction "P9.43_P9.43") (pintype "bidirectional"))
      (node (ref "R40") (pin "2") (pinfunction "2_2") (pintype "passive"))
    )
    (net (code "35") (name "Net-(Q2-G)") (class "Default")
      (node (ref "C10") (pin "1") (pinfunction "1_1") (pintype "passive"))
      (node (ref "Q2") (pin "1") (pinfunction "G_1") (pintype "passive"))
      (node (ref "R8") (pin "1") (pinfunction "1_1") (pintype "passive"))
    )
    (net (code "36") (name "Net-(Q3-G)") (class "Default")
      (node (ref "C11") (pin "1") (pinfunction "1_1") (pintype "passive"))
      (node (ref "Q3") (pin "1") (pinfunction "G_1") (pintype "passive"))
      (node (ref "R9") (pin "1") (pinfunction "1_1") (pintype "passive"))
    )
    (net (code "37") (name "Net-(Q4-G)") (class "Default")
      (node (ref "C12") (pin "1") (pinfunction "1_1") (pintype "passive"))
      (node (ref "Q4") (pin "1") (pinfunction "G_1") (pintype "passive"))
      (node (ref "R10") (pin "1") (pinfunction "1_1") (pintype "passive"))
    )
    (net (code "38") (name "Net-(Q5-G)") (class "Default")
      (node (ref "C13") (pin "1") (pinfunction "1_1") (pintype "passive"))
      (node (ref "Q5") (pin "1") (pinfunction "G_1") (pintype "passive"))
      (node (ref "R11") (pin "1") (pinfunction "1_1") (pintype "passive"))
    )
    (net (code "39") (name "Net-(Q6-S)") (class "Default")
      (node (ref "Q6") (pin "2") (pinfunction "S_2") (pintype "passive"))
      (node (ref "Q7") (pin "P$4") (pinfunction "G_P$4") (pintype "bidirectional"))
      (node (ref "R19") (pin "2") (pinfunction "2_2") (pintype "passive"))
      (node (ref "R20") (pin "1") (pinfunction "1_1") (pintype "passive"))
    )
    (net (code "40") (name "Net-(Q8-G)") (class "Default")
      (node (ref "Q8") (pin "P$4") (pinfunction "G_P$4") (pintype "bidirectional"))
      (node (ref "U1") (pin "27") (pinfunction "HIDRV_27") (pintype "bidirectional"))
    )
    (net (code "41") (name "Net-(Q9-G)") (class "Default")
      (node (ref "Q9") (pin "P$4") (pinfunction "G_P$4") (pintype "bidirectional"))
      (node (ref "U1") (pin "25") (pinfunction "LODRV_25") (pintype "bidirectional"))
    )
    (net (code "42") (name "Net-(Q12-D-PadP$5)") (class "Default")
      (node (ref "Q12") (pin "P$5") (pinfunction "D_P$5") (pintype "bidirectional"))
      (node (ref "Q12") (pin "P$6") (pinfunction "D_P$6") (pintype "bidirectional"))
      (node (ref "Q12") (pin "P$7") (pinfunction "D_P$7") (pintype "bidirectional"))
      (node (ref "Q12") (pin "P$8") (pinfunction "D_P$8") (pintype "bidirectional"))
      (node (ref "Q12") (pin "PAD") (pinfunction "D_PAD") (pintype "bidirectional"))
      (node (ref "Q13") (pin "P$5") (pinfunction "D_P$5") (pintype "bidirectional"))
      (node (ref "Q13") (pin "P$6") (pinfunction "D_P$6") (pintype "bidirectional"))
      (node (ref "Q13") (pin "P$7") (pinfunction "D_P$7") (pintype "bidirectional"))
      (node (ref "Q13") (pin "P$8") (pinfunction "D_P$8") (pintype "bidirectional"))
      (node (ref "Q13") (pin "PAD") (pinfunction "D_PAD") (pintype "bidirectional"))
    )
    (net (code "43") (name "Net-(Q12-G)") (class "Default")
      (node (ref "Q12") (pin "P$4") (pinfunction "G_P$4") (pintype "bidirectional"))
      (node (ref "R27") (pin "2") (pinfunction "2_2") (pintype "passive"))
      (node (ref "R29") (pin "1") (pinfunction "1_1") (pintype "passive"))
    )
    (net (code "44") (name "Net-(Q13-G)") (class "Default")
      (node (ref "Q13") (pin "P$4") (pinfunction "G_P$4") (pintype "bidirectional"))
      (node (ref "R28") (pin "2") (pinfunction "2_2") (pintype "passive"))
      (node (ref "R30") (pin "1") (pinfunction "1_1") (pintype "passive"))
    )
    (net (code "45") (name "Net-(Q14-G)") (class "Default")
      (node (ref "Q14") (pin "P$4") (pinfunction "G_P$4") (pintype "bidirectional"))
      (node (ref "U2") (pin "7") (pinfunction "HDRV_7") (pintype "passive"))
    )
    (net (code "46") (name "Net-(Q15-G)") (class "Default")
      (node (ref "Q15") (pin "P$4") (pinfunction "G_P$4") (pintype "bidirectional"))
      (node (ref "R44") (pin "1") (pinfunction "1_1") (pintype "passive"))
      (node (ref "U2") (pin "9") (pinfunction "LDRV/OC_9") (pintype "passive"))
    )
    (net (code "47") (name "Net-(U1-ACFET)") (class "Default")
      (node (ref "R19") (pin "1") (pinfunction "1_1") (pintype "passive"))
      (node (ref "U1") (pin "29") (pinfunction "ACFET_29") (pintype "bidirectional"))
    )
    (net (code "48") (name "Net-(U1-ACP)") (class "Default")
      (node (ref "R16") (pin "1") (pinfunction "1_1") (pintype "passive"))
      (node (ref "U1") (pin "31") (pinfunction "ACP_31") (pintype "bidirectional"))
    )
    (net (code "49") (name "Net-(U1-AFEFUSE)") (class "Default")
      (node (ref "R5") (pin "2") (pinfunction "2_2") (pintype "passive"))
      (node (ref "U1") (pin "21") (pinfunction "AFEFUSE_21") (pintype "bidirectional"))
    )
    (net (code "50") (name "Net-(U1-CHG)") (class "Default")
      (node (ref "R27") (pin "1") (pinfunction "1_1") (pintype "passive"))
      (node (ref "U1") (pin "32") (pinfunction "CHG_32") (pintype "bidirectional"))
    )
    (net (code "51") (name "Net-(U1-DSG)") (class "Default")
      (node (ref "R28") (pin "1") (pinfunction "1_1") (pintype "passive"))
      (node (ref "U1") (pin "30") (pinfunction "DSG_30") (pintype "bidirectional"))
    )
    (net (code "52") (name "Net-(U1-GPIO0)") (class "Default")
      (node (ref "R39") (pin "1") (pinfunction "1_1") (pintype "passive"))
      (node (ref "U1") (pin "14") (pinfunction "GPIO0_14") (pintype "bidirectional"))
    )
    (net (code "53") (name "Net-(U1-HSRN)") (class "Default")
      (node (ref "C22") (pin "2") (pinfunction "2_2") (pintype "passive"))
      (node (ref "C24") (pin "1") (pinfunction "1_1") (pintype "passive"))
      (node (ref "R31") (pin "P$4") (pinfunction "P$4_P$4") (pintype "bidirectional"))
      (node (ref "U1") (pin "19") (pinfunction "HSRN_19") (pintype "bidirectional"))
    )
    (net (code "54") (name "Net-(U1-HSRP)") (class "Default")
      (node (ref "C22") (pin "1") (pinfunction "1_1") (pintype "passive"))
      (node (ref "C23") (pin "1") (pinfunction "1_1") (pintype "passive"))
      (node (ref "R31") (pin "P$3") (pinfunction "P$3_P$3") (pintype "bidirectional"))
      (node (ref "U1") (pin "20") (pinfunction "HSRP_20") (pintype "bidirectional"))
    )
    (net (code "55") (name "Net-(U1-PBI)") (class "Default")
      (node (ref "C8") (pin "1") (pinfunction "1_1") (pintype "passive"))
      (node (ref "U1") (pin "2") (pinfunction "PBI_2") (pintype "bidirectional"))
    )
    (net (code "56") (name "Net-(U1-PH)") (class "Default")
      (node (ref "C21") (pin "2") (pinfunction "2_2") (pintype "passive"))
      (node (ref "L1") (pin "P$1") (pinfunction "P$1_P$1") (pintype "bidirectional"))
      (node (ref "Q8") (pin "P$1") (pinfunction "S_P$1") (pintype "bidirectional"))
      (node (ref "Q8") (pin "P$2") (pinfunction "S_P$2") (pintype "bidirectional"))
      (node (ref "Q8") (pin "P$3") (pinfunction "S_P$3") (pintype "bidirectional"))
      (node (ref "Q9") (pin "P$5") (pinfunction "D_P$5") (pintype "bidirectional"))
      (node (ref "Q9") (pin "P$6") (pinfunction "D_P$6") (pintype "bidirectional"))
      (node (ref "Q9") (pin "P$7") (pinfunction "D_P$7") (pintype "bidirectional"))
      (node (ref "Q9") (pin "P$8") (pinfunction "D_P$8") (pintype "bidirectional"))
      (node (ref "Q9") (pin "PAD") (pinfunction "D_PAD") (pintype "bidirectional"))
      (node (ref "U1") (pin "26") (pinfunction "PH_26") (pintype "bidirectional"))
    )
    (net (code "57") (name "Net-(U1-REGN)") (class "Default")
      (node (ref "C20") (pin "1") (pinfunction "1_1") (pintype "passive"))
      (node (ref "D2") (pin "1") (pinfunction "A_1") (pintype "passive"))
      (node (ref "D2") (pin "2") (pinfunction "A_2") (pintype "passive"))
      (node (ref "U1") (pin "23") (pinfunction "REGN_23") (pintype "bidirectional"))
    )
    (net (code "58") (name "Net-(U1-SMBC)") (class "Default")
      (node (ref "R37") (pin "1") (pinfunction "1_1") (pintype "passive"))
      (node (ref "U1") (pin "17") (pinfunction "SMBC_17") (pintype "bidirectional"))
    )
    (net (code "59") (name "Net-(U1-SMBD)") (class "Default")
      (node (ref "R35") (pin "1") (pinfunction "1_1") (pintype "passive"))
      (node (ref "U1") (pin "16") (pinfunction "SMBD_16") (pintype "bidirectional"))
    )
    (net (code "60") (name "Net-(U1-SRN)") (class "Default")
      (node (ref "C5") (pin "2") (pinfunction "2_2") (pintype "passive"))
      (node (ref "C6") (pin "2") (pinfunction "2_2") (pintype "passive"))
      (node (ref "R32") (pin "P$3") (pinfunction "P$3_P$3") (pintype "bidirectional"))
      (node (ref "U1") (pin "7") (pinfunction "SRN_7") (pintype "bidirectional"))
    )
    (net (code "61") (name "Net-(U1-SRP)") (class "Default")
      (node (ref "C5") (pin "1") (pinfunction "1_1") (pintype "passive"))
      (node (ref "C6") (pin "1") (pinfunction "1_1") (pintype "passive"))
      (node (ref "R32") (pin "P$4") (pinfunction "P$4_P$4") (pintype "bidirectional"))
      (node (ref "U1") (pin "8") (pinfunction "SRP_8") (pintype "bidirectional"))
    )
    (net (code "62") (name "Net-(U1-TS1)") (class "Default")
      (node (ref "J3") (pin "1") (pinfunction "1_1") (pintype "bidirectional"))
      (node (ref "R8") (pin "2") (pinfunction "2_2") (pintype "passive"))
      (node (ref "U1") (pin "10") (pinfunction "TS1_10") (pintype "bidirectional"))
    )
    (net (code "63") (name "Net-(U1-TS2)") (class "Default")
      (node (ref "J3") (pin "3") (pinfunction "3_3") (pintype "bidirectional"))
      (node (ref "R9") (pin "2") (pinfunction "2_2") (pintype "passive"))
      (node (ref "U1") (pin "11") (pinfunction "TS2_11") (pintype "bidirectional"))
    )
    (net (code "64") (name "Net-(U1-TS3)") (class "Default")
      (node (ref "J3") (pin "5") (pinfunction "5_5") (pintype "bidirectional"))
      (node (ref "R10") (pin "2") (pinfunction "2_2") (pintype "passive"))
      (node (ref "U1") (pin "12") (pinfunction "TS3_12") (pintype "bidirectional"))
    )
    (net (code "65") (name "Net-(U1-TS4)") (class "Default")
      (node (ref "J3") (pin "7") (pinfunction "7_7") (pintype "bidirectional"))
      (node (ref "R11") (pin "2") (pinfunction "2_2") (pintype "passive"))
      (node (ref "U1") (pin "13") (pinfunction "TS4_13") (pintype "bidirectional"))
    )
    (net (code "66") (name "Net-(U1-VC1)") (class "Default")
      (node (ref "C3") (pin "2") (pinfunction "2_2") (pintype "passive"))
      (node (ref "C4") (pin "1") (pinfunction "1_1") (pintype "passive"))
      (node (ref "R4") (pin "2") (pinfunction "2_2") (pintype "passive"))
      (node (ref "U1") (pin "6") (pinfunction "VC1_6") (pintype "bidirectional"))
    )
    (net (code "67") (name "Net-(U1-VC2)") (class "Default")
      (node (ref "C2") (pin "2") (pinfunction "2_2") (pintype "passive"))
      (node (ref "C3") (pin "1") (pinfunction "1_1") (pintype "passive"))
      (node (ref "R3") (pin "2") (pinfunction "2_2") (pintype "passive"))
      (node (ref "U1") (pin "5") (pinfunction "VC2_5") (pintype "bidirectional"))
    )
    (net (code "68") (name "Net-(U1-VC3)") (class "Default")
      (node (ref "C1") (pin "2") (pinfunction "2_2") (pintype "passive"))
      (node (ref "C2") (pin "1") (pinfunction "1_1") (pintype "passive"))
      (node (ref "R2") (pin "2") (pinfunction "2_2") (pintype "passive"))
      (node (ref "U1") (pin "4") (pinfunction "VC3_4") (pintype "bidirectional"))
    )
    (net (code "69") (name "Net-(U1-VC4)") (class "Default")
      (node (ref "C1") (pin "1") (pinfunction "1_1") (pintype "passive"))
      (node (ref "R1") (pin "2") (pinfunction "2_2") (pintype "passive"))
      (node (ref "U1") (pin "3") (pinfunction "VC4_3") (pintype "bidirectional"))
    )
    (net (code "70") (name "Net-(U1-VCC)") (class "Default")
      (node (ref "C17") (pin "1") (pinfunction "1_1") (pintype "passive"))
      (node (ref "R23") (pin "1") (pinfunction "1_1") (pintype "passive"))
      (node (ref "U1") (pin "22") (pinfunction "VCC_22") (pintype "bidirectional"))
    )
    (net (code "71") (name "Net-(U1-VFB)") (class "Default")
      (node (ref "C27") (pin "2") (pinfunction "2_2") (pintype "passive"))
      (node (ref "R33") (pin "1") (pinfunction "1_1") (pintype "passive"))
      (node (ref "R34") (pin "2") (pinfunction "2_2") (pintype "passive"))
      (node (ref "U1") (pin "18") (pinfunction "VFB_18") (pintype "bidirectional"))
    )
    (net (code "72") (name "Net-(U2-BOOT)") (class "Default")
      (node (ref "C34") (pin "1") (pinfunction "1_1") (pintype "passive"))
      (node (ref "U2") (pin "6") (pinfunction "BOOT_6") (pintype "passive"))
    )
    (net (code "73") (name "Net-(U2-BP)") (class "Default")
      (node (ref "C33") (pin "1") (pinfunction "1_1") (pintype "passive"))
      (node (ref "R13") (pin "2") (pinfunction "2_2") (pintype "passive"))
      (node (ref "U2") (pin "10") (pinfunction "BP_10") (pintype "passive"))
    )
    (net (code "74") (name "Net-(U2-COMP)") (class "Default")
      (node (ref "C31") (pin "1") (pinfunction "1_1") (pintype "passive"))
      (node (ref "C32") (pin "1") (pinfunction "1_1") (pintype "passive"))
      (node (ref "U2") (pin "4") (pinfunction "COMP_4") (pintype "passive"))
    )
    (net (code "75") (name "Net-(U2-EN{slash}SS)") (class "Default")
      (node (ref "C30") (pin "1") (pinfunction "1_1") (pintype "passive"))
      (node (ref "U2") (pin "2") (pinfunction "EN/SS_2") (pintype "passive"))
    )
    (net (code "76") (name "Net-(U2-FB)") (class "Default")
      (node (ref "C31") (pin "2") (pinfunction "2_2") (pintype "passive"))
      (node (ref "C35") (pin "2") (pinfunction "2_2") (pintype "passive"))
      (node (ref "R12") (pin "1") (pinfunction "1_1") (pintype "passive"))
      (node (ref "R15") (pin "1") (pinfunction "1_1") (pintype "passive"))
      (node (ref "R43") (pin "2") (pinfunction "2_2") (pintype "passive"))
      (node (ref "U2") (pin "5") (pinfunction "FB_5") (pintype "passive"))
    )
    (net (code "77") (name "Net-(U2-PGOOD)") (class "Default")
      (node (ref "R13") (pin "1") (pinfunction "1_1") (pintype "passive"))
      (node (ref "U2") (pin "3") (pinfunction "PGOOD_3") (pintype "passive"))
    )
    (net (code "78") (name "Net-(U2-SW)") (class "Default")
      (node (ref "C34") (pin "2") (pinfunction "2_2") (pintype "passive"))
      (node (ref "L2") (pin "P$1") (pinfunction "P$1_P$1") (pintype "bidirectional"))
      (node (ref "Q14") (pin "P$1") (pinfunction "S_P$1") (pintype "bidirectional"))
      (node (ref "Q14") (pin "P$2") (pinfunction "S_P$2") (pintype "bidirectional"))
      (node (ref "Q14") (pin "P$3") (pinfunction "S_P$3") (pintype "bidirectional"))
      (node (ref "Q15") (pin "P$5") (pinfunction "D_P$5") (pintype "bidirectional"))
      (node (ref "Q15") (pin "P$6") (pinfunction "D_P$6") (pintype "bidirectional"))
      (node (ref "Q15") (pin "P$7") (pinfunction "D_P$7") (pintype "bidirectional"))
      (node (ref "Q15") (pin "P$8") (pinfunction "D_P$8") (pintype "bidirectional"))
      (node (ref "Q15") (pin "PAD") (pinfunction "D_PAD") (pintype "bidirectional"))
      (node (ref "U2") (pin "8") (pinfunction "SW_8") (pintype "passive"))
    )
    (net (code "79") (name "unconnected-(PCB1-PadP8.1)") (class "Default")
      (node (ref "PCB1") (pin "P8.1") (pinfunction "P8.1_P8.1") (pintype "bidirectional"))
    )
    (net (code "80") (name "unconnected-(PCB1-PadP8.2)") (class "Default")
      (node (ref "PCB1") (pin "P8.2") (pinfunction "P8.2_P8.2") (pintype "bidirectional"))
    )
    (net (code "81") (name "unconnected-(PCB1-PadP8.3)") (class "Default")
      (node (ref "PCB1") (pin "P8.3") (pinfunction "P8.3_P8.3") (pintype "bidirectional"))
    )
    (net (code "82") (name "unconnected-(PCB1-PadP8.4)") (class "Default")
      (node (ref "PCB1") (pin "P8.4") (pinfunction "P8.4_P8.4") (pintype "bidirectional"))
    )
    (net (code "83") (name "unconnected-(PCB1-PadP8.5)") (class "Default")
      (node (ref "PCB1") (pin "P8.5") (pinfunction "P8.5_P8.5") (pintype "bidirectional"))
    )
    (net (code "84") (name "unconnected-(PCB1-PadP8.6)") (class "Default")
      (node (ref "PCB1") (pin "P8.6") (pinfunction "P8.6_P8.6") (pintype "bidirectional"))
    )
    (net (code "85") (name "unconnected-(PCB1-PadP8.7)") (class "Default")
      (node (ref "PCB1") (pin "P8.7") (pinfunction "P8.7_P8.7") (pintype "bidirectional"))
    )
    (net (code "86") (name "unconnected-(PCB1-PadP8.8)") (class "Default")
      (node (ref "PCB1") (pin "P8.8") (pinfunction "P8.8_P8.8") (pintype "bidirectional"))
    )
    (net (code "87") (name "unconnected-(PCB1-PadP8.9)") (class "Default")
      (node (ref "PCB1") (pin "P8.9") (pinfunction "P8.9_P8.9") (pintype "bidirectional"))
    )
    (net (code "88") (name "unconnected-(PCB1-PadP8.10)") (class "Default")
      (node (ref "PCB1") (pin "P8.10") (pinfunction "P8.10_P8.10") (pintype "bidirectional"))
    )
    (net (code "89") (name "unconnected-(PCB1-PadP8.11)") (class "Default")
      (node (ref "PCB1") (pin "P8.11") (pinfunction "P8.11_P8.11") (pintype "bidirectional"))
    )
    (net (code "90") (name "unconnected-(PCB1-PadP8.12)") (class "Default")
      (node (ref "PCB1") (pin "P8.12") (pinfunction "P8.12_P8.12") (pintype "bidirectional"))
    )
    (net (code "91") (name "unconnected-(PCB1-PadP8.13)") (class "Default")
      (node (ref "PCB1") (pin "P8.13") (pinfunction "P8.13_P8.13") (pintype "bidirectional"))
    )
    (net (code "92") (name "unconnected-(PCB1-PadP8.14)") (class "Default")
      (node (ref "PCB1") (pin "P8.14") (pinfunction "P8.14_P8.14") (pintype "bidirectional"))
    )
    (net (code "93") (name "unconnected-(PCB1-PadP8.15)") (class "Default")
      (node (ref "PCB1") (pin "P8.15") (pinfunction "P8.15_P8.15") (pintype "bidirectional"))
    )
    (net (code "94") (name "unconnected-(PCB1-PadP8.16)") (class "Default")
      (node (ref "PCB1") (pin "P8.16") (pinfunction "P8.16_P8.16") (pintype "bidirectional"))
    )
    (net (code "95") (name "unconnected-(PCB1-PadP8.17)") (class "Default")
      (node (ref "PCB1") (pin "P8.17") (pinfunction "P8.17_P8.17") (pintype "bidirectional"))
    )
    (net (code "96") (name "unconnected-(PCB1-PadP8.18)") (class "Default")
      (node (ref "PCB1") (pin "P8.18") (pinfunction "P8.18_P8.18") (pintype "bidirectional"))
    )
    (net (code "97") (name "unconnected-(PCB1-PadP8.19)") (class "Default")
      (node (ref "PCB1") (pin "P8.19") (pinfunction "P8.19_P8.19") (pintype "bidirectional"))
    )
    (net (code "98") (name "unconnected-(PCB1-PadP8.20)") (class "Default")
      (node (ref "PCB1") (pin "P8.20") (pinfunction "P8.20_P8.20") (pintype "bidirectional"))
    )
    (net (code "99") (name "unconnected-(PCB1-PadP8.21)") (class "Default")
      (node (ref "PCB1") (pin "P8.21") (pinfunction "P8.21_P8.21") (pintype "bidirectional"))
    )
    (net (code "100") (name "unconnected-(PCB1-PadP8.22)") (class "Default")
      (node (ref "PCB1") (pin "P8.22") (pinfunction "P8.22_P8.22") (pintype "bidirectional"))
    )
    (net (code "101") (name "unconnected-(PCB1-PadP8.23)") (class "Default")
      (node (ref "PCB1") (pin "P8.23") (pinfunction "P8.23_P8.23") (pintype "bidirectional"))
    )
    (net (code "102") (name "unconnected-(PCB1-PadP8.24)") (class "Default")
      (node (ref "PCB1") (pin "P8.24") (pinfunction "P8.24_P8.24") (pintype "bidirectional"))
    )
    (net (code "103") (name "unconnected-(PCB1-PadP8.25)") (class "Default")
      (node (ref "PCB1") (pin "P8.25") (pinfunction "P8.25_P8.25") (pintype "bidirectional"))
    )
    (net (code "104") (name "unconnected-(PCB1-PadP8.26)") (class "Default")
      (node (ref "PCB1") (pin "P8.26") (pinfunction "P8.26_P8.26") (pintype "bidirectional"))
    )
    (net (code "105") (name "unconnected-(PCB1-PadP8.27)") (class "Default")
      (node (ref "PCB1") (pin "P8.27") (pinfunction "P8.27_P8.27") (pintype "bidirectional"))
    )
    (net (code "106") (name "unconnected-(PCB1-PadP8.28)") (class "Default")
      (node (ref "PCB1") (pin "P8.28") (pinfunction "P8.28_P8.28") (pintype "bidirectional"))
    )
    (net (code "107") (name "unconnected-(PCB1-PadP8.29)") (class "Default")
      (node (ref "PCB1") (pin "P8.29") (pinfunction "P8.29_P8.29") (pintype "bidirectional"))
    )
    (net (code "108") (name "unconnected-(PCB1-PadP8.30)") (class "Default")
      (node (ref "PCB1") (pin "P8.30") (pinfunction "P8.30_P8.30") (pintype "bidirectional"))
    )
    (net (code "109") (name "unconnected-(PCB1-PadP8.31)") (class "Default")
      (node (ref "PCB1") (pin "P8.31") (pinfunction "P8.31_P8.31") (pintype "bidirectional"))
    )
    (net (code "110") (name "unconnected-(PCB1-PadP8.32)") (class "Default")
      (node (ref "PCB1") (pin "P8.32") (pinfunction "P8.32_P8.32") (pintype "bidirectional"))
    )
    (net (code "111") (name "unconnected-(PCB1-PadP8.33)") (class "Default")
      (node (ref "PCB1") (pin "P8.33") (pinfunction "P8.33_P8.33") (pintype "bidirectional"))
    )
    (net (code "112") (name "unconnected-(PCB1-PadP8.34)") (class "Default")
      (node (ref "PCB1") (pin "P8.34") (pinfunction "P8.34_P8.34") (pintype "bidirectional"))
    )
    (net (code "113") (name "unconnected-(PCB1-PadP8.35)") (class "Default")
      (node (ref "PCB1") (pin "P8.35") (pinfunction "P8.35_P8.35") (pintype "bidirectional"))
    )
    (net (code "114") (name "unconnected-(PCB1-PadP8.36)") (class "Default")
      (node (ref "PCB1") (pin "P8.36") (pinfunction "P8.36_P8.36") (pintype "bidirectional"))
    )
    (net (code "115") (name "unconnected-(PCB1-PadP8.37)") (class "Default")
      (node (ref "PCB1") (pin "P8.37") (pinfunction "P8.37_P8.37") (pintype "bidirectional"))
    )
    (net (code "116") (name "unconnected-(PCB1-PadP8.38)") (class "Default")
      (node (ref "PCB1") (pin "P8.38") (pinfunction "P8.38_P8.38") (pintype "bidirectional"))
    )
    (net (code "117") (name "unconnected-(PCB1-PadP8.39)") (class "Default")
      (node (ref "PCB1") (pin "P8.39") (pinfunction "P8.39_P8.39") (pintype "bidirectional"))
    )
    (net (code "118") (name "unconnected-(PCB1-PadP8.40)") (class "Default")
      (node (ref "PCB1") (pin "P8.40") (pinfunction "P8.40_P8.40") (pintype "bidirectional"))
    )
    (net (code "119") (name "unconnected-(PCB1-PadP8.41)") (class "Default")
      (node (ref "PCB1") (pin "P8.41") (pinfunction "P8.41_P8.41") (pintype "bidirectional"))
    )
    (net (code "120") (name "unconnected-(PCB1-PadP8.42)") (class "Default")
      (node (ref "PCB1") (pin "P8.42") (pinfunction "P8.42_P8.42") (pintype "bidirectional"))
    )
    (net (code "121") (name "unconnected-(PCB1-PadP8.43)") (class "Default")
      (node (ref "PCB1") (pin "P8.43") (pinfunction "P8.43_P8.43") (pintype "bidirectional"))
    )
    (net (code "122") (name "unconnected-(PCB1-PadP8.44)") (class "Default")
      (node (ref "PCB1") (pin "P8.44") (pinfunction "P8.44_P8.44") (pintype "bidirectional"))
    )
    (net (code "123") (name "unconnected-(PCB1-PadP8.45)") (class "Default")
      (node (ref "PCB1") (pin "P8.45") (pinfunction "P8.45_P8.45") (pintype "bidirectional"))
    )
    (net (code "124") (name "unconnected-(PCB1-PadP8.46)") (class "Default")
      (node (ref "PCB1") (pin "P8.46") (pinfunction "P8.46_P8.46") (pintype "bidirectional"))
    )
    (net (code "125") (name "unconnected-(PCB1-PadP9.7)") (class "Default")
      (node (ref "PCB1") (pin "P9.7") (pinfunction "P9.7_P9.7") (pintype "bidirectional"))
    )
    (net (code "126") (name "unconnected-(PCB1-PadP9.8)") (class "Default")
      (node (ref "PCB1") (pin "P9.8") (pinfunction "P9.8_P9.8") (pintype "bidirectional"))
    )
    (net (code "127") (name "unconnected-(PCB1-PadP9.10)") (class "Default")
      (node (ref "PCB1") (pin "P9.10") (pinfunction "P9.10_P9.10") (pintype "bidirectional"))
    )
    (net (code "128") (name "unconnected-(PCB1-PadP9.11)") (class "Default")
      (node (ref "PCB1") (pin "P9.11") (pinfunction "P9.11_P9.11") (pintype "bidirectional"))
    )
    (net (code "129") (name "unconnected-(PCB1-PadP9.12)") (class "Default")
      (node (ref "PCB1") (pin "P9.12") (pinfunction "P9.12_P9.12") (pintype "bidirectional"))
    )
    (net (code "130") (name "unconnected-(PCB1-PadP9.13)") (class "Default")
      (node (ref "PCB1") (pin "P9.13") (pinfunction "P9.13_P9.13") (pintype "bidirectional"))
    )
    (net (code "131") (name "unconnected-(PCB1-PadP9.14)") (class "Default")
      (node (ref "PCB1") (pin "P9.14") (pinfunction "P9.14_P9.14") (pintype "bidirectional"))
    )
    (net (code "132") (name "unconnected-(PCB1-PadP9.15)") (class "Default")
      (node (ref "PCB1") (pin "P9.15") (pinfunction "P9.15_P9.15") (pintype "bidirectional"))
    )
    (net (code "133") (name "unconnected-(PCB1-PadP9.16)") (class "Default")
      (node (ref "PCB1") (pin "P9.16") (pinfunction "P9.16_P9.16") (pintype "bidirectional"))
    )
    (net (code "134") (name "unconnected-(PCB1-PadP9.17)") (class "Default")
      (node (ref "PCB1") (pin "P9.17") (pinfunction "P9.17_P9.17") (pintype "bidirectional"))
    )
    (net (code "135") (name "unconnected-(PCB1-PadP9.18)") (class "Default")
      (node (ref "PCB1") (pin "P9.18") (pinfunction "P9.18_P9.18") (pintype "bidirectional"))
    )
    (net (code "136") (name "unconnected-(PCB1-PadP9.19)") (class "Default")
      (node (ref "PCB1") (pin "P9.19") (pinfunction "P9.19_P9.19") (pintype "bidirectional"))
    )
    (net (code "137") (name "unconnected-(PCB1-PadP9.20)") (class "Default")
      (node (ref "PCB1") (pin "P9.20") (pinfunction "P9.20_P9.20") (pintype "bidirectional"))
    )
    (net (code "138") (name "unconnected-(PCB1-PadP9.21)") (class "Default")
      (node (ref "PCB1") (pin "P9.21") (pinfunction "P9.21_P9.21") (pintype "bidirectional"))
    )
    (net (code "139") (name "unconnected-(PCB1-PadP9.22)") (class "Default")
      (node (ref "PCB1") (pin "P9.22") (pinfunction "P9.22_P9.22") (pintype "bidirectional"))
    )
    (net (code "140") (name "unconnected-(PCB1-PadP9.23)") (class "Default")
      (node (ref "PCB1") (pin "P9.23") (pinfunction "P9.23_P9.23") (pintype "bidirectional"))
    )
    (net (code "141") (name "unconnected-(PCB1-PadP9.25)") (class "Default")
      (node (ref "PCB1") (pin "P9.25") (pinfunction "P9.25_P9.25") (pintype "bidirectional"))
    )
    (net (code "142") (name "unconnected-(PCB1-PadP9.27)") (class "Default")
      (node (ref "PCB1") (pin "P9.27") (pinfunction "P9.27_P9.27") (pintype "bidirectional"))
    )
    (net (code "143") (name "unconnected-(PCB1-PadP9.28)") (class "Default")
      (node (ref "PCB1") (pin "P9.28") (pinfunction "P9.28_P9.28") (pintype "bidirectional"))
    )
    (net (code "144") (name "unconnected-(PCB1-PadP9.29)") (class "Default")
      (node (ref "PCB1") (pin "P9.29") (pinfunction "P9.29_P9.29") (pintype "bidirectional"))
    )
    (net (code "145") (name "unconnected-(PCB1-PadP9.30)") (class "Default")
      (node (ref "PCB1") (pin "P9.30") (pinfunction "P9.30_P9.30") (pintype "bidirectional"))
    )
    (net (code "146") (name "unconnected-(PCB1-PadP9.31)") (class "Default")
      (node (ref "PCB1") (pin "P9.31") (pinfunction "P9.31_P9.31") (pintype "bidirectional"))
    )
    (net (code "147") (name "unconnected-(PCB1-PadP9.32)") (class "Default")
      (node (ref "PCB1") (pin "P9.32") (pinfunction "P9.32_P9.32") (pintype "bidirectional"))
    )
    (net (code "148") (name "unconnected-(PCB1-PadP9.33)") (class "Default")
      (node (ref "PCB1") (pin "P9.33") (pinfunction "P9.33_P9.33") (pintype "bidirectional"))
    )
    (net (code "149") (name "unconnected-(PCB1-PadP9.34)") (class "Default")
      (node (ref "PCB1") (pin "P9.34") (pinfunction "P9.34_P9.34") (pintype "bidirectional"))
    )
    (net (code "150") (name "unconnected-(PCB1-PadP9.35)") (class "Default")
      (node (ref "PCB1") (pin "P9.35") (pinfunction "P9.35_P9.35") (pintype "bidirectional"))
    )
    (net (code "151") (name "unconnected-(PCB1-PadP9.36)") (class "Default")
      (node (ref "PCB1") (pin "P9.36") (pinfunction "P9.36_P9.36") (pintype "bidirectional"))
    )
    (net (code "152") (name "unconnected-(PCB1-PadP9.37)") (class "Default")
      (node (ref "PCB1") (pin "P9.37") (pinfunction "P9.37_P9.37") (pintype "bidirectional"))
    )
    (net (code "153") (name "unconnected-(PCB1-PadP9.38)") (class "Default")
      (node (ref "PCB1") (pin "P9.38") (pinfunction "P9.38_P9.38") (pintype "bidirectional"))
    )
    (net (code "154") (name "unconnected-(PCB1-PadP9.39)") (class "Default")
      (node (ref "PCB1") (pin "P9.39") (pinfunction "P9.39_P9.39") (pintype "bidirectional"))
    )
    (net (code "155") (name "unconnected-(PCB1-PadP9.40)") (class "Default")
      (node (ref "PCB1") (pin "P9.40") (pinfunction "P9.40_P9.40") (pintype "bidirectional"))
    )
    (net (code "156") (name "unconnected-(PCB1-PadP9.41)") (class "Default")
      (node (ref "PCB1") (pin "P9.41") (pinfunction "P9.41_P9.41") (pintype "bidirectional"))
    )
    (net (code "157") (name "unconnected-(PCB1-PadP9.42)") (class "Default")
      (node (ref "PCB1") (pin "P9.42") (pinfunction "P9.42_P9.42") (pintype "bidirectional"))
    )
  )
)
